# lis3dh_smd_v402.net
KiCad netlist of a schematic drawn in EAGLE
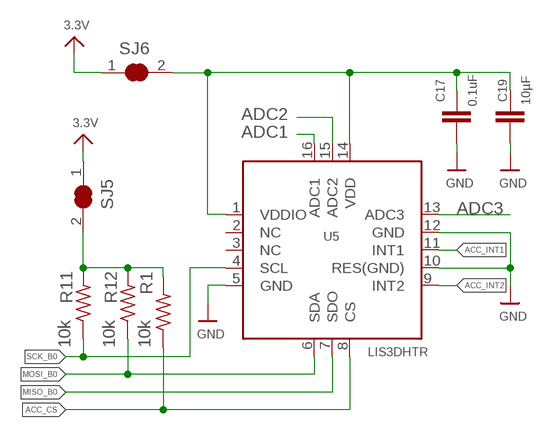
[diagram p0: schematic, sheet 1]

(export (version "E")
  (design (tool "Eeschema 10.0.6"))
  (components
    (comp (ref "C17")
      (value "0.1uF")
      (footprint "eagle-import:C0402")
      (libsource (lib "eagle-import") (part "C-EUC0402"))
    )
    (comp (ref "C19")
      (value "10µF")
      (footprint "eagle-import:C0402")
      (libsource (lib "eagle-import") (part "C-EUC0402"))
    )
    (comp (ref "R1")
      (value "10k")
      (footprint "eagle-import:R0402")
      (libsource (lib "eagle-import") (part "R-US_R0402"))
    )
    (comp (ref "R11")
      (value "10k")
      (footprint "eagle-import:R0402")
      (libsource (lib "eagle-import") (part "R-US_R0402"))
    )
    (comp (ref "R12")
      (value "10k")
      (footprint "eagle-import:R0402")
      (libsource (lib "eagle-import") (part "R-US_R0402"))
    )
    (comp (ref "SJ5")
      (value "SOLDERJUMPER_CLOSED")
      (footprint "eagle-import:SOLDERJUMPER_CLOSEDWIRE")
      (libsource (lib "eagle-import") (part "SOLDERJUMPER_CLOSED"))
    )
    (comp (ref "SJ6")
      (value "SOLDERJUMPER_CLOSED")
      (footprint "eagle-import:SOLDERJUMPER_CLOSEDWIRE")
      (libsource (lib "eagle-import") (part "SOLDERJUMPER_CLOSED"))
    )
    (comp (ref "U5")
      (value "LIS3DHTR")
      (footprint "eagle-import:LGA16_3X3MM")
      (libsource (lib "eagle-import") (part "ACCEL_LIS3DHTR"))
    )
  )
  (nets
    (net (code "1") (name "/ADC1") (class "Default")
      (node (ref "U5") (pin "16") (pinfunction "ADC1_16") (pintype "input"))
    )
    (net (code "2") (name "/ADC2") (class "Default")
      (node (ref "U5") (pin "15") (pinfunction "ADC2_15") (pintype "input"))
    )
    (net (code "3") (name "/ADC3") (class "Default")
      (node (ref "U5") (pin "13") (pinfunction "ADC3_13") (pintype "input"))
    )
    (net (code "4") (name "3.3V") (class "Default")
      (node (ref "SJ5") (pin "1") (pinfunction "1_1") (pintype "passive"))
      (node (ref "SJ6") (pin "1") (pinfunction "1_1") (pintype "passive"))
    )
    (net (code "5") (name "ACC_CS") (class "Default")
      (node (ref "R1") (pin "1") (pinfunction "1_1") (pintype "passive"))
      (node (ref "U5") (pin "8") (pinfunction "CS_8") (pintype "input"))
    )
    (net (code "6") (name "ACC_INT1") (class "Default")
      (node (ref "U5") (pin "11") (pinfunction "INT1_11") (pintype "output"))
    )
    (net (code "7") (name "ACC_INT2") (class "Default")
      (node (ref "U5") (pin "9") (pinfunction "INT2_9") (pintype "output"))
    )
    (net (code "8") (name "GND") (class "Default")
      (node (ref "C17") (pin "2") (pinfunction "2_2") (pintype "passive"))
      (node (ref "C19") (pin "2") (pinfunction "2_2") (pintype "passive"))
      (node (ref "U5") (pin "10") (pinfunction "RES(GND)_10") (pintype "bidirectional"))
      (node (ref "U5") (pin "12") (pinfunction "GND_12") (pintype "power_in"))
      (node (ref "U5") (pin "5") (pinfunction "GND_5") (pintype "power_in"))
    )
    (net (code "9") (name "MISO_B0") (class "Default")
      (node (ref "U5") (pin "7") (pinfunction "SDO_7") (pintype "bidirectional"))
    )
    (net (code "10") (name "MOSI_B0") (class "Default")
      (node (ref "R12") (pin "1") (pinfunction "1_1") (pintype "passive"))
      (node (ref "U5") (pin "6") (pinfunction "SDA_6") (pintype "bidirectional"))
    )
    (net (code "11") (name "Net-(R1-Pad2)") (class "Default")
      (node (ref "R1") (pin "2") (pinfunction "2_2") (pintype "passive"))
      (node (ref "R11") (pin "2") (pinfunction "2_2") (pintype "passive"))
      (node (ref "R12") (pin "2") (pinfunction "2_2") (pintype "passive"))
      (node (ref "SJ5") (pin "2") (pinfunction "2_2") (pintype "passive"))
    )
    (net (code "12") (name "Net-(U5-VDD)") (class "Default")
      (node (ref "C17") (pin "1") (pinfunction "1_1") (pintype "passive"))
      (node (ref "C19") (pin "1") (pinfunction "1_1") (pintype "passive"))
      (node (ref "SJ6") (pin "2") (pinfunction "2_2") (pintype "passive"))
      (node (ref "U5") (pin "1") (pinfunction "VDDIO_1") (pintype "power_in"))
      (node (ref "U5") (pin "14") (pinfunction "VDD_14") (pintype "power_in"))
    )
    (net (code "13") (name "SCK_B0") (class "Default")
      (node (ref "R11") (pin "1") (pinfunction "1_1") (pintype "passive"))
      (node (ref "U5") (pin "4") (pinfunction "SCL_4") (pintype "bidirectional"))
    )
    (net (code "14") (name "unconnected-(U5-NC-Pad2)") (class "Default")
      (node (ref "U5") (pin "2") (pinfunction "NC_2") (pintype "no_connect"))
    )
    (net (code "15") (name "unconnected-(U5-NC-Pad3)") (class "Default")
      (node (ref "U5") (pin "3") (pinfunction "NC_3") (pintype "no_connect"))
    )
  )
)
